# CharlieplexedLarsonScannerWandBreakout.net
KiCad netlist of a schematic drawn in EAGLE
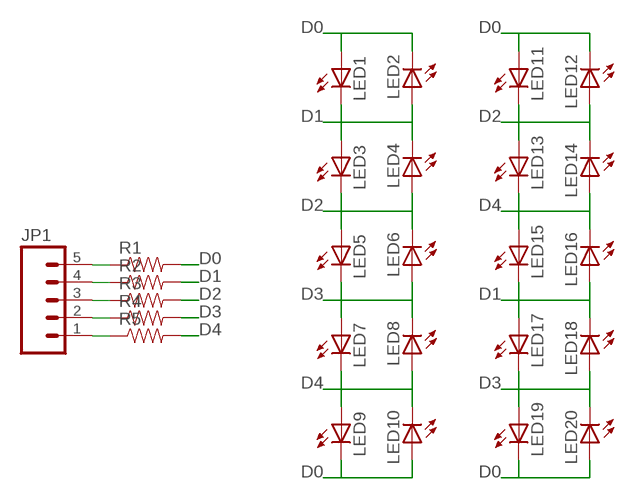
[diagram p0: schematic, sheet 1]

(export (version "E")
  (design (tool "Eeschema 10.0.6"))
  (components
    (comp (ref "JP1")
      (value "M05PTH")
      (footprint "eagle-import:1X05")
      (libsource (lib "eagle-import") (part "M05PTH"))
    )
    (comp (ref "LED1")
      (value "LEDOVAL")
      (footprint "eagle-import:LED-OVAL")
      (libsource (lib "eagle-import") (part "LEDOVAL"))
    )
    (comp (ref "LED2")
      (value "LEDOVAL")
      (footprint "eagle-import:LED-OVAL")
      (libsource (lib "eagle-import") (part "LEDOVAL"))
    )
    (comp (ref "LED3")
      (value "LEDOVAL")
      (footprint "eagle-import:LED-OVAL")
      (libsource (lib "eagle-import") (part "LEDOVAL"))
    )
    (comp (ref "LED4")
      (value "LEDOVAL")
      (footprint "eagle-import:LED-OVAL")
      (libsource (lib "eagle-import") (part "LEDOVAL"))
    )
    (comp (ref "LED5")
      (value "LEDOVAL")
      (footprint "eagle-import:LED-OVAL")
      (libsource (lib "eagle-import") (part "LEDOVAL"))
    )
    (comp (ref "LED6")
      (value "LEDOVAL")
      (footprint "eagle-import:LED-OVAL")
      (libsource (lib "eagle-import") (part "LEDOVAL"))
    )
    (comp (ref "LED7")
      (value "LEDOVAL")
      (footprint "eagle-import:LED-OVAL")
      (libsource (lib "eagle-import") (part "LEDOVAL"))
    )
    (comp (ref "LED8")
      (value "LEDOVAL")
      (footprint "eagle-import:LED-OVAL")
      (libsource (lib "eagle-import") (part "LEDOVAL"))
    )
    (comp (ref "LED9")
      (value "LEDOVAL")
      (footprint "eagle-import:LED-OVAL")
      (libsource (lib "eagle-import") (part "LEDOVAL"))
    )
    (comp (ref "LED10")
      (value "LEDOVAL")
      (footprint "eagle-import:LED-OVAL")
      (libsource (lib "eagle-import") (part "LEDOVAL"))
    )
    (comp (ref "LED11")
      (value "LEDOVAL")
      (footprint "eagle-import:LED-OVAL")
      (libsource (lib "eagle-import") (part "LEDOVAL"))
    )
    (comp (ref "LED12")
      (value "LEDOVAL")
      (footprint "eagle-import:LED-OVAL")
      (libsource (lib "eagle-import") (part "LEDOVAL"))
    )
    (comp (ref "LED13")
      (value "LEDOVAL")
      (footprint "eagle-import:LED-OVAL")
      (libsource (lib "eagle-import") (part "LEDOVAL"))
    )
    (comp (ref "LED14")
      (value "LEDOVAL")
      (footprint "eagle-import:LED-OVAL")
      (libsource (lib "eagle-import") (part "LEDOVAL"))
    )
    (comp (ref "LED15")
      (value "LEDOVAL")
      (footprint "eagle-import:LED-OVAL")
      (libsource (lib "eagle-import") (part "LEDOVAL"))
    )
    (comp (ref "LED16")
      (value "LEDOVAL")
      (footprint "eagle-import:LED-OVAL")
      (libsource (lib "eagle-import") (part "LEDOVAL"))
    )
    (comp (ref "LED17")
      (value "LEDOVAL")
      (footprint "eagle-import:LED-OVAL")
      (libsource (lib "eagle-import") (part "LEDOVAL"))
    )
    (comp (ref "LED18")
      (value "LEDOVAL")
      (footprint "eagle-import:LED-OVAL")
      (libsource (lib "eagle-import") (part "LEDOVAL"))
    )
    (comp (ref "LED19")
      (value "LEDOVAL")
      (footprint "eagle-import:LED-OVAL")
      (libsource (lib "eagle-import") (part "LEDOVAL"))
    )
    (comp (ref "LED20")
      (value "LEDOVAL")
      (footprint "eagle-import:LED-OVAL")
      (libsource (lib "eagle-import") (part "LEDOVAL"))
    )
    (comp (ref "R1")
      (value "RESISTORAXIAL-0.3")
      (footprint "eagle-import:AXIAL-0.3")
      (libsource (lib "eagle-import") (part "RESISTORAXIAL-0.3"))
    )
    (comp (ref "R2")
      (value "RESISTORAXIAL-0.3")
      (footprint "eagle-import:AXIAL-0.3")
      (libsource (lib "eagle-import") (part "RESISTORAXIAL-0.3"))
    )
    (comp (ref "R3")
      (value "RESISTORAXIAL-0.3")
      (footprint "eagle-import:AXIAL-0.3")
      (libsource (lib "eagle-import") (part "RESISTORAXIAL-0.3"))
    )
    (comp (ref "R4")
      (value "RESISTORAXIAL-0.3")
      (footprint "eagle-import:AXIAL-0.3")
      (libsource (lib "eagle-import") (part "RESISTORAXIAL-0.3"))
    )
    (comp (ref "R5")
      (value "RESISTORAXIAL-0.3")
      (footprint "eagle-import:AXIAL-0.3")
      (libsource (lib "eagle-import") (part "RESISTORAXIAL-0.3"))
    )
  )
  (nets
    (net (code "1") (name "/D0") (class "Default")
      (node (ref "LED1") (pin "ANODE") (pinfunction "A_ANODE") (pintype "passive"))
      (node (ref "LED10") (pin "ANODE") (pinfunction "A_ANODE") (pintype "passive"))
      (node (ref "LED11") (pin "ANODE") (pinfunction "A_ANODE") (pintype "passive"))
      (node (ref "LED12") (pin "CATHODE") (pinfunction "C_CATHODE") (pintype "passive"))
      (node (ref "LED19") (pin "CATHODE") (pinfunction "C_CATHODE") (pintype "passive"))
      (node (ref "LED2") (pin "CATHODE") (pinfunction "C_CATHODE") (pintype "passive"))
      (node (ref "LED20") (pin "ANODE") (pinfunction "A_ANODE") (pintype "passive"))
      (node (ref "LED9") (pin "CATHODE") (pinfunction "C_CATHODE") (pintype "passive"))
      (node (ref "R1") (pin "P$2") (pinfunction "2_P$2") (pintype "passive"))
    )
    (net (code "2") (name "/D1") (class "Default")
      (node (ref "LED1") (pin "CATHODE") (pinfunction "C_CATHODE") (pintype "passive"))
      (node (ref "LED15") (pin "CATHODE") (pinfunction "C_CATHODE") (pintype "passive"))
      (node (ref "LED16") (pin "ANODE") (pinfunction "A_ANODE") (pintype "passive"))
      (node (ref "LED17") (pin "ANODE") (pinfunction "A_ANODE") (pintype "passive"))
      (node (ref "LED18") (pin "CATHODE") (pinfunction "C_CATHODE") (pintype "passive"))
      (node (ref "LED2") (pin "ANODE") (pinfunction "A_ANODE") (pintype "passive"))
      (node (ref "LED3") (pin "ANODE") (pinfunction "A_ANODE") (pintype "passive"))
      (node (ref "LED4") (pin "CATHODE") (pinfunction "C_CATHODE") (pintype "passive"))
      (node (ref "R2") (pin "P$2") (pinfunction "2_P$2") (pintype "passive"))
    )
    (net (code "3") (name "/D2") (class "Default")
      (node (ref "LED11") (pin "CATHODE") (pinfunction "C_CATHODE") (pintype "passive"))
      (node (ref "LED12") (pin "ANODE") (pinfunction "A_ANODE") (pintype "passive"))
      (node (ref "LED13") (pin "ANODE") (pinfunction "A_ANODE") (pintype "passive"))
      (node (ref "LED14") (pin "CATHODE") (pinfunction "C_CATHODE") (pintype "passive"))
      (node (ref "LED3") (pin "CATHODE") (pinfunction "C_CATHODE") (pintype "passive"))
      (node (ref "LED4") (pin "ANODE") (pinfunction "A_ANODE") (pintype "passive"))
      (node (ref "LED5") (pin "ANODE") (pinfunction "A_ANODE") (pintype "passive"))
      (node (ref "LED6") (pin "CATHODE") (pinfunction "C_CATHODE") (pintype "passive"))
      (node (ref "R3") (pin "P$2") (pinfunction "2_P$2") (pintype "passive"))
    )
    (net (code "4") (name "/D3") (class "Default")
      (node (ref "LED17") (pin "CATHODE") (pinfunction "C_CATHODE") (pintype "passive"))
      (node (ref "LED18") (pin "ANODE") (pinfunction "A_ANODE") (pintype "passive"))
      (node (ref "LED19") (pin "ANODE") (pinfunction "A_ANODE") (pintype "passive"))
      (node (ref "LED20") (pin "CATHODE") (pinfunction "C_CATHODE") (pintype "passive"))
      (node (ref "LED5") (pin "CATHODE") (pinfunction "C_CATHODE") (pintype "passive"))
      (node (ref "LED6") (pin "ANODE") (pinfunction "A_ANODE") (pintype "passive"))
      (node (ref "LED7") (pin "ANODE") (pinfunction "A_ANODE") (pintype "passive"))
      (node (ref "LED8") (pin "CATHODE") (pinfunction "C_CATHODE") (pintype "passive"))
      (node (ref "R4") (pin "P$2") (pinfunction "2_P$2") (pintype "passive"))
    )
    (net (code "5") (name "/D4") (class "Default")
      (node (ref "LED10") (pin "CATHODE") (pinfunction "C_CATHODE") (pintype "passive"))
      (node (ref "LED13") (pin "CATHODE") (pinfunction "C_CATHODE") (pintype "passive"))
      (node (ref "LED14") (pin "ANODE") (pinfunction "A_ANODE") (pintype "passive"))
      (node (ref "LED15") (pin "ANODE") (pinfunction "A_ANODE") (pintype "passive"))
      (node (ref "LED16") (pin "CATHODE") (pinfunction "C_CATHODE") (pintype "passive"))
      (node (ref "LED7") (pin "CATHODE") (pinfunction "C_CATHODE") (pintype "passive"))
      (node (ref "LED8") (pin "ANODE") (pinfunction "A_ANODE") (pintype "passive"))
      (node (ref "LED9") (pin "ANODE") (pinfunction "A_ANODE") (pintype "passive"))
      (node (ref "R5") (pin "P$2") (pinfunction "2_P$2") (pintype "passive"))
    )
    (net (code "6") (name "Net-(R1-1)") (class "Default")
      (node (ref "JP1") (pin "5") (pinfunction "5_5") (pintype "passive"))
      (node (ref "R1") (pin "P$1") (pinfunction "1_P$1") (pintype "passive"))
    )
    (net (code "7") (name "Net-(R2-1)") (class "Default")
      (node (ref "JP1") (pin "4") (pinfunction "4_4") (pintype "passive"))
      (node (ref "R2") (pin "P$1") (pinfunction "1_P$1") (pintype "passive"))
    )
    (net (code "8") (name "Net-(R3-1)") (class "Default")
      (node (ref "JP1") (pin "3") (pinfunction "3_3") (pintype "passive"))
      (node (ref "R3") (pin "P$1") (pinfunction "1_P$1") (pintype "passive"))
    )
    (net (code "9") (name "Net-(R4-1)") (class "Default")
      (node (ref "JP1") (pin "2") (pinfunction "2_2") (pintype "passive"))
      (node (ref "R4") (pin "P$1") (pinfunction "1_P$1") (pintype "passive"))
    )
    (net (code "10") (name "Net-(R5-1)") (class "Default")
      (node (ref "JP1") (pin "1") (pinfunction "1_1") (pintype "passive"))
      (node (ref "R5") (pin "P$1") (pinfunction "1_P$1") (pintype "passive"))
    )
  )
)
